# TouScruino-avr-ui2-v0.net
KiCad netlist of a schematic drawn in EAGLE
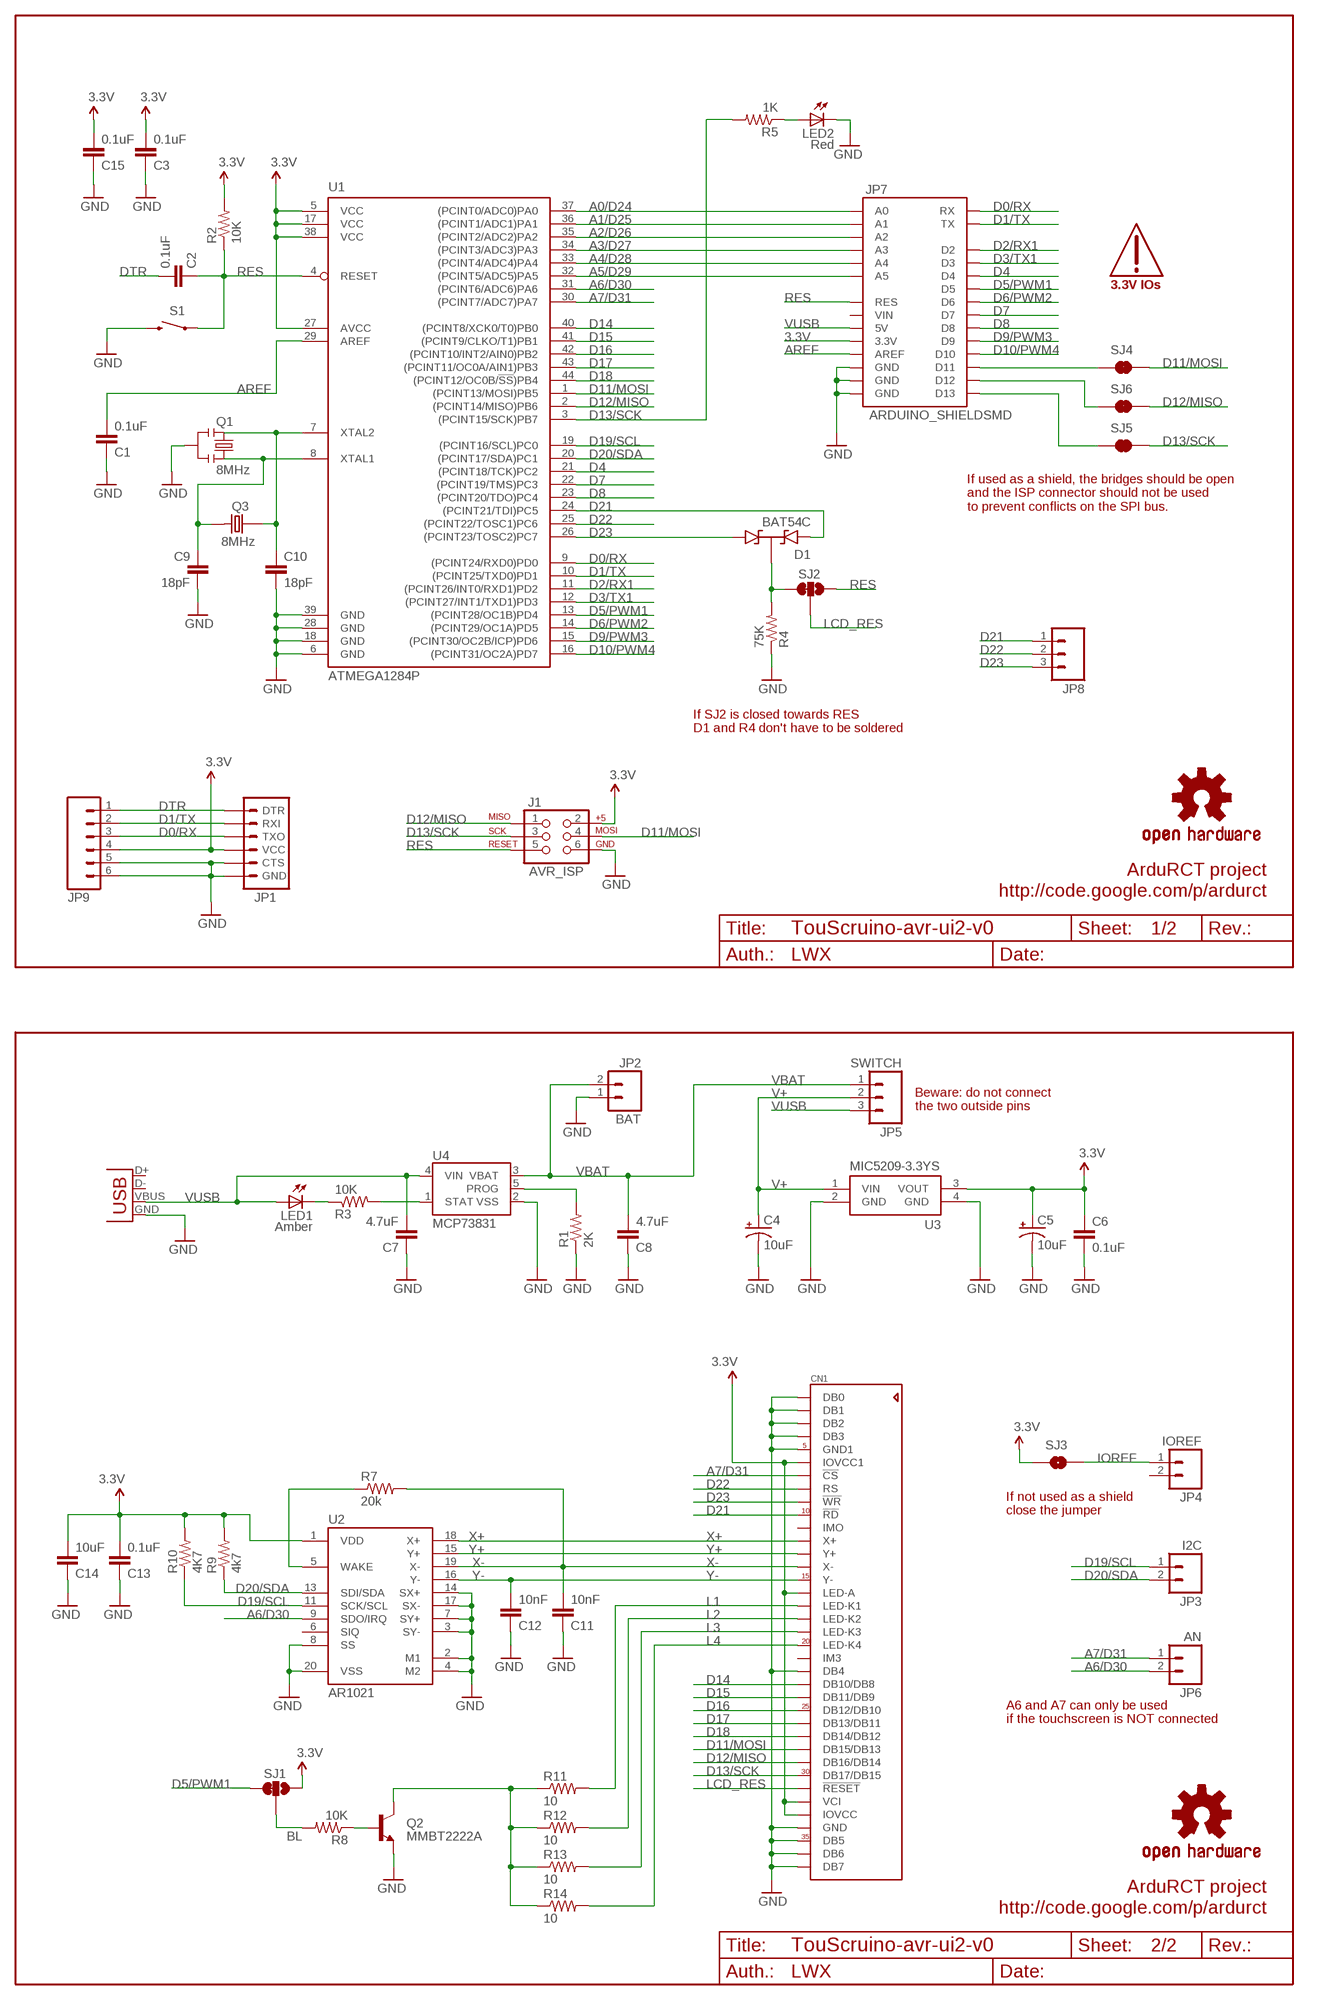
[diagram p0: schematic, sheet 1]

(export (version "E")
  (design (tool "Eeschema 10.0.6"))
  (components
    (comp (ref "C1")
      (value "0.1uF")
      (footprint "eagle-import:0805")
      (libsource (lib "eagle-import") (part "CAP0805"))
    )
    (comp (ref "C2")
      (value "0.1uF")
      (footprint "eagle-import:0805")
      (libsource (lib "eagle-import") (part "CAP0805"))
    )
    (comp (ref "C3")
      (value "0.1uF")
      (footprint "eagle-import:0805")
      (libsource (lib "eagle-import") (part "CAP0805"))
    )
    (comp (ref "C4")
      (value "10uF")
      (footprint "eagle-import:EIA3216")
      (libsource (lib "eagle-import") (part "CAP_POL1206"))
    )
    (comp (ref "C5")
      (value "10uF")
      (footprint "eagle-import:EIA3216")
      (libsource (lib "eagle-import") (part "CAP_POL1206"))
    )
    (comp (ref "C6")
      (value "0.1uF")
      (footprint "eagle-import:0805")
      (libsource (lib "eagle-import") (part "CAP0805"))
    )
    (comp (ref "C7")
      (value "4.7uF")
      (footprint "eagle-import:0805")
      (libsource (lib "eagle-import") (part "CAP0805"))
    )
    (comp (ref "C8")
      (value "4.7uF")
      (footprint "eagle-import:0805")
      (libsource (lib "eagle-import") (part "CAP0805"))
    )
    (comp (ref "C9")
      (value "18pF")
      (footprint "eagle-import:0603-CAP")
      (libsource (lib "eagle-import") (part "CAP0603-CAP"))
    )
    (comp (ref "C10")
      (value "18pF")
      (footprint "eagle-import:0603-CAP")
      (libsource (lib "eagle-import") (part "CAP0603-CAP"))
    )
    (comp (ref "C11")
      (value "10nF")
      (footprint "eagle-import:0805")
      (libsource (lib "eagle-import") (part "CAP0805"))
    )
    (comp (ref "C12")
      (value "10nF")
      (footprint "eagle-import:0805")
      (libsource (lib "eagle-import") (part "CAP0805"))
    )
    (comp (ref "C13")
      (value "0.1uF")
      (footprint "eagle-import:0805")
      (libsource (lib "eagle-import") (part "CAP0805"))
    )
    (comp (ref "C14")
      (value "10uF")
      (footprint "eagle-import:0805")
      (libsource (lib "eagle-import") (part "CAP0805"))
    )
    (comp (ref "C15")
      (value "0.1uF")
      (footprint "eagle-import:0805")
      (libsource (lib "eagle-import") (part "CAP0805"))
    )
    (comp (ref "CN1")
      (value "ILI9325_LCD1.0MM")
      (footprint "eagle-import:ILI9325_28INCH_TS")
      (libsource (lib "eagle-import") (part "ILI9325_LCD1.0MM"))
    )
    (comp (ref "D1")
      (value "BAT54C")
      (footprint "eagle-import:SOT23-3")
      (libsource (lib "eagle-import") (part "BAT54C"))
    )
    (comp (ref "J1")
      (value "AVR_ISP")
      (footprint "eagle-import:2X3")
      (libsource (lib "eagle-import") (part "AVR_SPI_PRG_6PTH"))
    )
    (comp (ref "JP1")
      (value "ARDUINO_SERIAL_PROGRAMPTH")
      (footprint "eagle-import:1X06")
      (libsource (lib "eagle-import") (part "ARDUINO_SERIAL_PROGRAMPTH"))
    )
    (comp (ref "JP2")
      (value "BAT")
      (footprint "eagle-import:JST-2-SMD")
      (libsource (lib "eagle-import") (part "M02-JST-2MM-SMT"))
    )
    (comp (ref "JP3")
      (value "I2C")
      (footprint "eagle-import:1X02_SMD")
      (libsource (lib "eagle-import") (part "M02SMD2"))
    )
    (comp (ref "JP4")
      (value "IOREF")
      (footprint "eagle-import:1X02_SMD")
      (libsource (lib "eagle-import") (part "M02SMD2"))
    )
    (comp (ref "JP5")
      (value "SWITCH")
      (footprint "eagle-import:1X03_SMD_TH")
      (libsource (lib "eagle-import") (part "M03SMD_TH"))
    )
    (comp (ref "JP6")
      (value "AN")
      (footprint "eagle-import:1X02")
      (libsource (lib "eagle-import") (part "M02"))
    )
    (comp (ref "JP7")
      (value "ARDUINO_SHIELDSMD")
      (footprint "eagle-import:ARDUINO_SHIELD_SMD")
      (libsource (lib "eagle-import") (part "ARDUINO_SHIELDSMD"))
    )
    (comp (ref "JP8")
      (value "M03PTH")
      (footprint "eagle-import:1X03")
      (libsource (lib "eagle-import") (part "M03PTH"))
    )
    (comp (ref "JP9")
      (value "M06SMD")
      (footprint "eagle-import:1X06-SMD")
      (libsource (lib "eagle-import") (part "M06SMD"))
    )
    (comp (ref "LED1")
      (value "Amber")
      (footprint "eagle-import:LED")
      (libsource (lib "eagle-import") (part "LED"))
    )
    (comp (ref "LED2")
      (value "Red")
      (footprint "eagle-import:LED")
      (libsource (lib "eagle-import") (part "LED"))
    )
    (comp (ref "Q1")
      (value "8MHz")
      (footprint "eagle-import:RESONATOR-SMD")
      (libsource (lib "eagle-import") (part "RESONATORSMD"))
    )
    (comp (ref "Q2")
      (value "MMBT2222A")
      (footprint "eagle-import:SOT23-3")
      (libsource (lib "eagle-import") (part "TRANSISTOR_NPNSOT23-3"))
    )
    (comp (ref "Q3")
      (value "8MHz")
      (footprint "eagle-import:CRYSTAL_5X3.2")
      (libsource (lib "eagle-import") (part "CRYSTAL_5X3.2"))
    )
    (comp (ref "R1")
      (value "2K")
      (footprint "eagle-import:0805")
      (libsource (lib "eagle-import") (part "RESISTOR0805-RES"))
    )
    (comp (ref "R2")
      (value "10K")
      (footprint "eagle-import:0805")
      (libsource (lib "eagle-import") (part "RESISTOR0805-RES"))
    )
    (comp (ref "R3")
      (value "10K")
      (footprint "eagle-import:0805")
      (libsource (lib "eagle-import") (part "RESISTOR0805-RES"))
    )
    (comp (ref "R4")
      (value "75K")
      (footprint "eagle-import:0805")
      (libsource (lib "eagle-import") (part "RESISTOR0805-RES"))
    )
    (comp (ref "R5")
      (value "1K")
      (footprint "eagle-import:0805")
      (libsource (lib "eagle-import") (part "RESISTOR0805-RES"))
    )
    (comp (ref "R7")
      (value "20k")
      (footprint "eagle-import:0805")
      (libsource (lib "eagle-import") (part "RESISTOR0805-RES"))
    )
    (comp (ref "R8")
      (value "10K")
      (footprint "eagle-import:0805")
      (libsource (lib "eagle-import") (part "RESISTOR0805-RES"))
    )
    (comp (ref "R9")
      (value "4k7")
      (footprint "eagle-import:0805")
      (libsource (lib "eagle-import") (part "RESISTOR0805-RES"))
    )
    (comp (ref "R10")
      (value "4K7")
      (footprint "eagle-import:0805")
      (libsource (lib "eagle-import") (part "RESISTOR0805-RES"))
    )
    (comp (ref "R11")
      (value "10")
      (footprint "eagle-import:0805")
      (libsource (lib "eagle-import") (part "RESISTOR0805-RES"))
    )
    (comp (ref "R12")
      (value "10")
      (footprint "eagle-import:0805")
      (libsource (lib "eagle-import") (part "RESISTOR0805-RES"))
    )
    (comp (ref "R13")
      (value "10")
      (footprint "eagle-import:0805")
      (libsource (lib "eagle-import") (part "RESISTOR0805-RES"))
    )
    (comp (ref "R14")
      (value "10")
      (footprint "eagle-import:0805")
      (libsource (lib "eagle-import") (part "RESISTOR0805-RES"))
    )
    (comp (ref "S1")
      (value "SWITCH-MOMENTARY-2SMD")
      (footprint "eagle-import:TACTILE_SWITCH_SMD")
      (libsource (lib "eagle-import") (part "SWITCH-MOMENTARY-2SMD"))
    )
    (comp (ref "SJ1")
      (value "SJ_2WAYS_1-2")
      (footprint "eagle-import:SJ_2WAYS_1-2_S")
      (libsource (lib "eagle-import") (part "SJ_2WAYS_1-2"))
    )
    (comp (ref "SJ2")
      (value "SJ_2WAYS_1-2")
      (footprint "eagle-import:SJ_2WAYS_1-2_S")
      (libsource (lib "eagle-import") (part "SJ_2WAYS_1-2"))
    )
    (comp (ref "SJ3")
      (value "SOLDERJUMPERNO")
      (footprint "eagle-import:SJ_2S-NO")
      (libsource (lib "eagle-import") (part "SOLDERJUMPERNO"))
    )
    (comp (ref "SJ4")
      (value "SOLDERJUMPERTRACE")
      (footprint "eagle-import:SJ_2S-TRACE")
      (libsource (lib "eagle-import") (part "SOLDERJUMPERTRACE"))
    )
    (comp (ref "SJ5")
      (value "SOLDERJUMPERTRACE")
      (footprint "eagle-import:SJ_2S-TRACE")
      (libsource (lib "eagle-import") (part "SOLDERJUMPERTRACE"))
    )
    (comp (ref "SJ6")
      (value "SOLDERJUMPERTRACE")
      (footprint "eagle-import:SJ_2S-TRACE")
      (libsource (lib "eagle-import") (part "SOLDERJUMPERTRACE"))
    )
    (comp (ref "U$3")
      (value "OSHW-LOGOM")
      (footprint "eagle-import:OSHW-LOGO-M")
      (libsource (lib "eagle-import") (part "OSHW-LOGOM"))
    )
    (comp (ref "U$4")
      (value "3.3V_IO")
      (footprint "eagle-import:3.3V_IO")
      (libsource (lib "eagle-import") (part "3.3V_IO"))
    )
    (comp (ref "U$5")
      (value "OSHW-LOGOM")
      (footprint "eagle-import:OSHW-LOGO-M")
      (libsource (lib "eagle-import") (part "OSHW-LOGOM"))
    )
    (comp (ref "U1")
      (value "ATMEGA1284P")
      (footprint "eagle-import:TQFP44")
      (libsource (lib "eagle-import") (part "ATMEGA324A"))
    )
    (comp (ref "U2")
      (value "AR1021")
      (footprint "eagle-import:SSOP20")
      (libsource (lib "eagle-import") (part "AR1020"))
    )
    (comp (ref "U3")
      (value "MIC5209-3.3YS")
      (footprint "eagle-import:SOT223")
      (libsource (lib "eagle-import") (part "MIC5209"))
    )
    (comp (ref "U4")
      (value "MCP73831")
      (footprint "eagle-import:SOT23-5")
      (libsource (lib "eagle-import") (part "MCP73831"))
    )
    (comp (ref "X2")
      (value "USB")
      (footprint "eagle-import:USB-MICROB")
      (libsource (lib "eagle-import") (part "USB"))
    )
  )
  (nets
    (net (code "1") (name "/A0{slash}D24") (class "Default")
      (node (ref "JP7") (pin "A0") (pinfunction "A0_A0") (pintype "bidirectional"))
      (node (ref "U1") (pin "37") (pinfunction "(PCINT0/ADC0)PA0_37") (pintype "bidirectional"))
    )
    (net (code "2") (name "/A1{slash}D25") (class "Default")
      (node (ref "JP7") (pin "A1") (pinfunction "A1_A1") (pintype "bidirectional"))
      (node (ref "U1") (pin "36") (pinfunction "(PCINT1/ADC1)PA1_36") (pintype "bidirectional"))
    )
    (net (code "3") (name "/A2{slash}D26") (class "Default")
      (node (ref "JP7") (pin "A2") (pinfunction "A2_A2") (pintype "bidirectional"))
      (node (ref "U1") (pin "35") (pinfunction "(PCINT2/ADC2)PA2_35") (pintype "bidirectional"))
    )
    (net (code "4") (name "/A3{slash}D27") (class "Default")
      (node (ref "JP7") (pin "A3") (pinfunction "A3_A3") (pintype "bidirectional"))
      (node (ref "U1") (pin "34") (pinfunction "(PCINT3/ADC3)PA3_34") (pintype "bidirectional"))
    )
    (net (code "5") (name "/A4{slash}D28") (class "Default")
      (node (ref "JP7") (pin "A4") (pinfunction "A4_A4") (pintype "bidirectional"))
      (node (ref "U1") (pin "33") (pinfunction "(PCINT4/ADC4)PA4_33") (pintype "bidirectional"))
    )
    (net (code "6") (name "/A5{slash}D29") (class "Default")
      (node (ref "JP7") (pin "A5") (pinfunction "A5_A5") (pintype "bidirectional"))
      (node (ref "U1") (pin "32") (pinfunction "(PCINT5/ADC5)PA5_32") (pintype "bidirectional"))
    )
    (net (code "7") (name "/A6{slash}D30") (class "Default")
      (node (ref "JP6") (pin "2") (pinfunction "2_2") (pintype "passive"))
      (node (ref "U1") (pin "31") (pinfunction "(PCINT6/ADC6)PA6_31") (pintype "bidirectional"))
      (node (ref "U2") (pin "9") (pinfunction "SDO/IRQ_9") (pintype "bidirectional"))
    )
    (net (code "8") (name "/A7{slash}D31") (class "Default")
      (node (ref "CN1") (pin "7") (pinfunction "~{CS}_7") (pintype "passive"))
      (node (ref "JP6") (pin "1") (pinfunction "1_1") (pintype "passive"))
      (node (ref "U1") (pin "30") (pinfunction "(PCINT7/ADC7)PA7_30") (pintype "bidirectional"))
    )
    (net (code "9") (name "/AREF") (class "Default")
      (node (ref "C1") (pin "2") (pinfunction "2_2") (pintype "passive"))
      (node (ref "JP7") (pin "AREF") (pinfunction "AREF_AREF") (pintype "bidirectional"))
      (node (ref "U1") (pin "29") (pinfunction "AREF_29") (pintype "passive"))
    )
    (net (code "10") (name "/BL") (class "Default")
      (node (ref "R8") (pin "2") (pinfunction "2_2") (pintype "passive"))
      (node (ref "SJ1") (pin "2") (pinfunction "2_2") (pintype "passive"))
    )
    (net (code "11") (name "/D0{slash}RX") (class "Default")
      (node (ref "JP1") (pin "3") (pinfunction "TXO_3") (pintype "passive"))
      (node (ref "JP7") (pin "RX") (pinfunction "RX_RX") (pintype "bidirectional"))
      (node (ref "JP9") (pin "3") (pinfunction "3_3") (pintype "passive"))
      (node (ref "U1") (pin "9") (pinfunction "(PCINT24/RXD0)PD0_9") (pintype "bidirectional"))
    )
    (net (code "12") (name "/D1{slash}TX") (class "Default")
      (node (ref "JP1") (pin "2") (pinfunction "RXI_2") (pintype "passive"))
      (node (ref "JP7") (pin "TX") (pinfunction "TX_TX") (pintype "bidirectional"))
      (node (ref "JP9") (pin "2") (pinfunction "2_2") (pintype "passive"))
      (node (ref "U1") (pin "10") (pinfunction "(PCINT25/TXD0)PD1_10") (pintype "bidirectional"))
    )
    (net (code "13") (name "/D2{slash}RX1") (class "Default")
      (node (ref "JP7") (pin "D2") (pinfunction "D2_D2") (pintype "bidirectional"))
      (node (ref "U1") (pin "11") (pinfunction "(PCINT26/INT0/RXD1)PD2_11") (pintype "bidirectional"))
    )
    (net (code "14") (name "/D3{slash}TX1") (class "Default")
      (node (ref "JP7") (pin "D3") (pinfunction "D3_D3") (pintype "bidirectional"))
      (node (ref "U1") (pin "12") (pinfunction "(PCINT27/INT1/TXD1)PD3_12") (pintype "bidirectional"))
    )
    (net (code "15") (name "/D4") (class "Default")
      (node (ref "JP7") (pin "D4") (pinfunction "D4_D4") (pintype "bidirectional"))
      (node (ref "U1") (pin "21") (pinfunction "(PCINT18/TCK)PC2_21") (pintype "output"))
    )
    (net (code "16") (name "/D5{slash}PWM1") (class "Default")
      (node (ref "JP7") (pin "D5") (pinfunction "D5_D5") (pintype "bidirectional"))
      (node (ref "SJ1") (pin "1") (pinfunction "1_1") (pintype "passive"))
      (node (ref "U1") (pin "13") (pinfunction "(PCINT28/OC1B)PD4_13") (pintype "bidirectional"))
    )
    (net (code "17") (name "/D6{slash}PWM2") (class "Default")
      (node (ref "JP7") (pin "D6") (pinfunction "D6_D6") (pintype "bidirectional"))
      (node (ref "U1") (pin "14") (pinfunction "(PCINT29/OC1A)PD5_14") (pintype "bidirectional"))
    )
    (net (code "18") (name "/D7") (class "Default")
      (node (ref "JP7") (pin "D7") (pinfunction "D7_D7") (pintype "bidirectional"))
      (node (ref "U1") (pin "22") (pinfunction "(PCINT19/TMS)PC3_22") (pintype "output"))
    )
    (net (code "19") (name "/D8") (class "Default")
      (node (ref "JP7") (pin "D8") (pinfunction "D8_D8") (pintype "bidirectional"))
      (node (ref "U1") (pin "23") (pinfunction "(PCINT20/TDO)PC4_23") (pintype "output"))
    )
    (net (code "20") (name "/D9{slash}PWM3") (class "Default")
      (node (ref "JP7") (pin "D9") (pinfunction "D9_D9") (pintype "bidirectional"))
      (node (ref "U1") (pin "15") (pinfunction "(PCINT30/OC2B/ICP)PD6_15") (pintype "bidirectional"))
    )
    (net (code "21") (name "/D10{slash}PWM4") (class "Default")
      (node (ref "JP7") (pin "D10") (pinfunction "D10_D10") (pintype "bidirectional"))
      (node (ref "U1") (pin "16") (pinfunction "(PCINT31/OC2A)PD7_16") (pintype "bidirectional"))
    )
    (net (code "22") (name "/D11{slash}MOSI") (class "Default")
      (node (ref "CN1") (pin "28") (pinfunction "DB15/DB13_28") (pintype "passive"))
      (node (ref "J1") (pin "4") (pinfunction "4_4") (pintype "passive"))
      (node (ref "SJ4") (pin "2") (pinfunction "2_2") (pintype "passive"))
      (node (ref "U1") (pin "1") (pinfunction "(PCINT13/MOSI)PB5_1") (pintype "bidirectional"))
    )
    (net (code "23") (name "/D12{slash}MISO") (class "Default")
      (node (ref "CN1") (pin "29") (pinfunction "DB16/DB14_29") (pintype "passive"))
      (node (ref "J1") (pin "1") (pinfunction "1_1") (pintype "passive"))
      (node (ref "SJ6") (pin "2") (pinfunction "2_2") (pintype "passive"))
      (node (ref "U1") (pin "2") (pinfunction "(PCINT14/MISO)PB6_2") (pintype "bidirectional"))
    )
    (net (code "24") (name "/D13{slash}SCK") (class "Default")
      (node (ref "CN1") (pin "30") (pinfunction "DB17/DB15_30") (pintype "passive"))
      (node (ref "J1") (pin "3") (pinfunction "3_3") (pintype "passive"))
      (node (ref "R5") (pin "2") (pinfunction "2_2") (pintype "passive"))
      (node (ref "SJ5") (pin "2") (pinfunction "2_2") (pintype "passive"))
      (node (ref "U1") (pin "3") (pinfunction "(PCINT15/SCK)PB7_3") (pintype "bidirectional"))
    )
    (net (code "25") (name "/D14") (class "Default")
      (node (ref "CN1") (pin "23") (pinfunction "DB10/DB8_23") (pintype "passive"))
      (node (ref "U1") (pin "40") (pinfunction "(PCINT8/XCK0/T0)PB0_40") (pintype "bidirectional"))
    )
    (net (code "26") (name "/D15") (class "Default")
      (node (ref "CN1") (pin "24") (pinfunction "DB11/DB9_24") (pintype "passive"))
      (node (ref "U1") (pin "41") (pinfunction "(PCINT9/CLKO/T1)PB1_41") (pintype "bidirectional"))
    )
    (net (code "27") (name "/D16") (class "Default")
      (node (ref "CN1") (pin "25") (pinfunction "DB12/DB10_25") (pintype "passive"))
      (node (ref "U1") (pin "42") (pinfunction "(PCINT10/INT2/AIN0)PB2_42") (pintype "bidirectional"))
    )
    (net (code "28") (name "/D17") (class "Default")
      (node (ref "CN1") (pin "26") (pinfunction "DB13/DB11_26") (pintype "passive"))
      (node (ref "U1") (pin "43") (pinfunction "(PCINT11/OC0A/AIN1)PB3_43") (pintype "bidirectional"))
    )
    (net (code "29") (name "/D18") (class "Default")
      (node (ref "CN1") (pin "27") (pinfunction "DB14/DB12_27") (pintype "passive"))
      (node (ref "U1") (pin "44") (pinfunction "(PCINT12/OC0B/~{SS})PB4_44") (pintype "bidirectional"))
    )
    (net (code "30") (name "/D19{slash}SCL") (class "Default")
      (node (ref "JP3") (pin "1") (pinfunction "1_1") (pintype "passive"))
      (node (ref "R10") (pin "1") (pinfunction "1_1") (pintype "passive"))
      (node (ref "U1") (pin "19") (pinfunction "(PCINT16/SCL)PC0_19") (pintype "output"))
      (node (ref "U2") (pin "11") (pinfunction "SCK/SCL_11") (pintype "bidirectional"))
    )
    (net (code "31") (name "/D20{slash}SDA") (class "Default")
      (node (ref "JP3") (pin "2") (pinfunction "2_2") (pintype "passive"))
      (node (ref "R9") (pin "1") (pinfunction "1_1") (pintype "passive"))
      (node (ref "U1") (pin "20") (pinfunction "(PCINT17/SDA)PC1_20") (pintype "output"))
      (node (ref "U2") (pin "13") (pinfunction "SDI/SDA_13") (pintype "bidirectional"))
    )
    (net (code "32") (name "/D21") (class "Default")
      (node (ref "CN1") (pin "10") (pinfunction "~{RD}_10") (pintype "passive"))
      (node (ref "D1") (pin "2") (pinfunction "A2_2") (pintype "bidirectional"))
      (node (ref "JP8") (pin "1") (pinfunction "1_1") (pintype "passive"))
      (node (ref "U1") (pin "24") (pinfunction "(PCINT21/TDI)PC5_24") (pintype "output"))
    )
    (net (code "33") (name "/D22") (class "Default")
      (node (ref "CN1") (pin "8") (pinfunction "RS_8") (pintype "passive"))
      (node (ref "JP8") (pin "2") (pinfunction "2_2") (pintype "passive"))
      (node (ref "U1") (pin "25") (pinfunction "(PCINT22/TOSC1)PC6_25") (pintype "output"))
    )
    (net (code "34") (name "/D23") (class "Default")
      (node (ref "CN1") (pin "9") (pinfunction "~{WR}_9") (pintype "passive"))
      (node (ref "D1") (pin "1") (pinfunction "A1_1") (pintype "bidirectional"))
      (node (ref "JP8") (pin "3") (pinfunction "3_3") (pintype "passive"))
      (node (ref "U1") (pin "26") (pinfunction "(PCINT23/TOSC2)PC7_26") (pintype "output"))
    )
    (net (code "35") (name "/DTR") (class "Default")
      (node (ref "C2") (pin "2") (pinfunction "2_2") (pintype "passive"))
      (node (ref "JP1") (pin "1") (pinfunction "DTR_1") (pintype "passive"))
      (node (ref "JP9") (pin "1") (pinfunction "1_1") (pintype "passive"))
    )
    (net (code "36") (name "/IOREF") (class "Default")
      (node (ref "JP4") (pin "1") (pinfunction "1_1") (pintype "passive"))
      (node (ref "SJ3") (pin "2") (pinfunction "2_2") (pintype "passive"))
    )
    (net (code "37") (name "/L1") (class "Default")
      (node (ref "CN1") (pin "17") (pinfunction "LED-K1_17") (pintype "passive"))
      (node (ref "R11") (pin "2") (pinfunction "2_2") (pintype "passive"))
    )
    (net (code "38") (name "/L2") (class "Default")
      (node (ref "CN1") (pin "18") (pinfunction "LED-K2_18") (pintype "passive"))
      (node (ref "R12") (pin "2") (pinfunction "2_2") (pintype "passive"))
    )
    (net (code "39") (name "/L3") (class "Default")
      (node (ref "CN1") (pin "19") (pinfunction "LED-K3_19") (pintype "passive"))
      (node (ref "R13") (pin "2") (pinfunction "2_2") (pintype "passive"))
    )
    (net (code "40") (name "/L4") (class "Default")
      (node (ref "CN1") (pin "20") (pinfunction "LED-K4_20") (pintype "passive"))
      (node (ref "R14") (pin "2") (pinfunction "2_2") (pintype "passive"))
    )
    (net (code "41") (name "/LCD_RES") (class "Default")
      (node (ref "CN1") (pin "31") (pinfunction "~{RESET}_31") (pintype "passive"))
      (node (ref "SJ2") (pin "2") (pinfunction "2_2") (pintype "passive"))
    )
    (net (code "42") (name "/RES") (class "Default")
      (node (ref "C2") (pin "1") (pinfunction "1_1") (pintype "passive"))
      (node (ref "J1") (pin "5") (pinfunction "5_5") (pintype "passive"))
      (node (ref "JP7") (pin "RES") (pinfunction "RES_RES") (pintype "bidirectional"))
      (node (ref "R2") (pin "1") (pinfunction "1_1") (pintype "passive"))
      (node (ref "S1") (pin "1") (pinfunction "1_1") (pintype "passive"))
      (node (ref "SJ2") (pin "3") (pinfunction "3_3") (pintype "passive"))
      (node (ref "U1") (pin "4") (pinfunction "RESET_4") (pintype "input"))
    )
    (net (code "43") (name "/V+") (class "Default")
      (node (ref "C4") (pin "A") (pinfunction "+_A") (pintype "passive"))
      (node (ref "JP5") (pin "2") (pinfunction "2_2") (pintype "passive"))
      (node (ref "U3") (pin "1") (pinfunction "VIN_1") (pintype "bidirectional"))
    )
    (net (code "44") (name "/VBAT") (class "Default")
      (node (ref "C8") (pin "2") (pinfunction "2_2") (pintype "passive"))
      (node (ref "JP2") (pin "2") (pinfunction "2_2") (pintype "passive"))
      (node (ref "JP5") (pin "1") (pinfunction "1_1") (pintype "passive"))
      (node (ref "U4") (pin "3") (pinfunction "VBAT_3") (pintype "power_in"))
    )
    (net (code "45") (name "/VUSB") (class "Default")
      (node (ref "C7") (pin "2") (pinfunction "2_2") (pintype "passive"))
      (node (ref "JP5") (pin "3") (pinfunction "3_3") (pintype "passive"))
      (node (ref "JP7") (pin "5V") (pinfunction "5V_5V") (pintype "bidirectional"))
      (node (ref "LED1") (pin "A1") (pinfunction "A_A1") (pintype "passive"))
      (node (ref "U4") (pin "4") (pinfunction "VIN_4") (pintype "power_in"))
      (node (ref "X2") (pin "VBUS") (pinfunction "VBUS_VBUS") (pintype "bidirectional"))
    )
    (net (code "46") (name "/X+") (class "Default")
      (node (ref "CN1") (pin "12") (pinfunction "X+_12") (pintype "passive"))
      (node (ref "U2") (pin "18") (pinfunction "X+_18") (pintype "bidirectional"))
    )
    (net (code "47") (name "/X-") (class "Default")
      (node (ref "C11") (pin "2") (pinfunction "2_2") (pintype "passive"))
      (node (ref "CN1") (pin "14") (pinfunction "X-_14") (pintype "passive"))
      (node (ref "R7") (pin "2") (pinfunction "2_2") (pintype "passive"))
      (node (ref "U2") (pin "19") (pinfunction "X-_19") (pintype "bidirectional"))
    )
    (net (code "48") (name "/Y+") (class "Default")
      (node (ref "CN1") (pin "13") (pinfunction "Y+_13") (pintype "passive"))
      (node (ref "U2") (pin "15") (pinfunction "Y+_15") (pintype "bidirectional"))
    )
    (net (code "49") (name "/Y-") (class "Default")
      (node (ref "C12") (pin "2") (pinfunction "2_2") (pintype "passive"))
      (node (ref "CN1") (pin "15") (pinfunction "Y-_15") (pintype "passive"))
      (node (ref "U2") (pin "16") (pinfunction "Y-_16") (pintype "bidirectional"))
    )
    (net (code "50") (name "3.3V") (class "Default")
      (node (ref "C13") (pin "2") (pinfunction "2_2") (pintype "passive"))
      (node (ref "C14") (pin "2") (pinfunction "2_2") (pintype "passive"))
      (node (ref "C15") (pin "2") (pinfunction "2_2") (pintype "passive"))
      (node (ref "C3") (pin "2") (pinfunction "2_2") (pintype "passive"))
      (node (ref "C5") (pin "A") (pinfunction "+_A") (pintype "passive"))
      (node (ref "C6") (pin "1") (pinfunction "1_1") (pintype "passive"))
      (node (ref "CN1") (pin "16") (pinfunction "LED-A_16") (pintype "passive"))
      (node (ref "CN1") (pin "32") (pinfunction "VCI_32") (pintype "power_in"))
      (node (ref "CN1") (pin "33") (pinfunction "IOVCC_33") (pintype "power_in"))
      (node (ref "CN1") (pin "6") (pinfunction "IOVCC1_6") (pintype "power_in"))
      (node (ref "J1") (pin "2") (pinfunction "2_2") (pintype "passive"))
      (node (ref "JP1") (pin "4") (pinfunction "VCC_4") (pintype "passive"))
      (node (ref "JP7") (pin "3.3V") (pinfunction "3.3V_3.3V") (pintype "bidirectional"))
      (node (ref "JP9") (pin "4") (pinfunction "4_4") (pintype "passive"))
      (node (ref "R10") (pin "2") (pinfunction "2_2") (pintype "passive"))
      (node (ref "R2") (pin "2") (pinfunction "2_2") (pintype "passive"))
      (node (ref "R9") (pin "2") (pinfunction "2_2") (pintype "passive"))
      (node (ref "SJ1") (pin "3") (pinfunction "3_3") (pintype "passive"))
      (node (ref "SJ3") (pin "1") (pinfunction "1_1") (pintype "passive"))
      (node (ref "U1") (pin "17") (pinfunction "VCC_17") (pintype "power_in"))
      (node (ref "U1") (pin "27") (pinfunction "AVCC_27") (pintype "power_in"))
      (node (ref "U1") (pin "38") (pinfunction "VCC_38") (pintype "power_in"))
      (node (ref "U1") (pin "5") (pinfunction "VCC_5") (pintype "power_in"))
      (node (ref "U2") (pin "1") (pinfunction "VDD_1") (pintype "bidirectional"))
      (node (ref "U3") (pin "3") (pinfunction "VOUT_3") (pintype "bidirectional"))
    )
    (net (code "51") (name "GND") (class "Default")
      (node (ref "C1") (pin "1") (pinfunction "1_1") (pintype "passive"))
      (node (ref "C10") (pin "2") (pinfunction "2_2") (pintype "passive"))
      (node (ref "C11") (pin "1") (pinfunction "1_1") (pintype "passive"))
      (node (ref "C12") (pin "1") (pinfunction "1_1") (pintype "passive"))
      (node (ref "C13") (pin "1") (pinfunction "1_1") (pintype "passive"))
      (node (ref "C14") (pin "1") (pinfunction "1_1") (pintype "passive"))
      (node (ref "C15") (pin "1") (pinfunction "1_1") (pintype "passive"))
      (node (ref "C3") (pin "1") (pinfunction "1_1") (pintype "passive"))
      (node (ref "C4") (pin "C") (pinfunction "-_C") (pintype "passive"))
      (node (ref "C5") (pin "C") (pinfunction "-_C") (pintype "passive"))
      (node (ref "C6") (pin "2") (pinfunction "2_2") (pintype "passive"))
      (node (ref "C7") (pin "1") (pinfunction "1_1") (pintype "passive"))
      (node (ref "C8") (pin "1") (pinfunction "1_1") (pintype "passive"))
      (node (ref "C9") (pin "2") (pinfunction "2_2") (pintype "passive"))
      (node (ref "CN1") (pin "1") (pinfunction "DB0_1") (pintype "passive"))
      (node (ref "CN1") (pin "2") (pinfunction "DB1_2") (pintype "passive"))
      (node (ref "CN1") (pin "22") (pinfunction "DB4_22") (pintype "passive"))
      (node (ref "CN1") (pin "3") (pinfunction "DB2_3") (pintype "passive"))
      (node (ref "CN1") (pin "34") (pinfunction "GND_34") (pintype "power_in"))
      (node (ref "CN1") (pin "35") (pinfunction "DB5_35") (pintype "passive"))
      (node (ref "CN1") (pin "36") (pinfunction "DB6_36") (pintype "passive"))
      (node (ref "CN1") (pin "37") (pinfunction "DB7_37") (pintype "passive"))
      (node (ref "CN1") (pin "4") (pinfunction "DB3_4") (pintype "passive"))
      (node (ref "CN1") (pin "5") (pinfunction "GND1_5") (pintype "power_in"))
      (node (ref "J1") (pin "6") (pinfunction "6_6") (pintype "passive"))
      (node (ref "JP1") (pin "5") (pinfunction "CTS_5") (pintype "passive"))
      (node (ref "JP1") (pin "6") (pinfunction "GND_6") (pintype "passive"))
      (node (ref "JP2") (pin "1") (pinfunction "1_1") (pintype "passive"))
      (node (ref "JP7") (pin "GND@0") (pinfunction "GND_GND@0") (pintype "bidirectional"))
      (node (ref "JP7") (pin "GND@1") (pinfunction "GND_GND@1") (pintype "bidirectional"))
      (node (ref "JP7") (pin "GND@2") (pinfunction "GND_GND@2") (pintype "bidirectional"))
      (node (ref "JP9") (pin "5") (pinfunction "5_5") (pintype "passive"))
      (node (ref "JP9") (pin "6") (pinfunction "6_6") (pintype "passive"))
      (node (ref "LED2") (pin "C1") (pinfunction "C_C1") (pintype "passive"))
      (node (ref "Q1") (pin "2") (pinfunction "2_2") (pintype "passive"))
      (node (ref "Q2") (pin "2") (pinfunction "E_2") (pintype "passive"))
      (node (ref "R1") (pin "1") (pinfunction "1_1") (pintype "passive"))
      (node (ref "R4") (pin "1") (pinfunction "1_1") (pintype "passive"))
      (node (ref "S1") (pin "3") (pinfunction "2_3") (pintype "passive"))
      (node (ref "U1") (pin "18") (pinfunction "GND_18") (pintype "power_in"))
      (node (ref "U1") (pin "28") (pinfunction "GND_28") (pintype "power_in"))
      (node (ref "U1") (pin "39") (pinfunction "GND_39") (pintype "power_in"))
      (node (ref "U1") (pin "6") (pinfunction "GND_6") (pintype "power_in"))
      (node (ref "U2") (pin "14") (pinfunction "SX+_14") (pintype "bidirectional"))
      (node (ref "U2") (pin "17") (pinfunction "SX-_17") (pintype "bidirectional"))
      (node (ref "U2") (pin "2") (pinfunction "M1_2") (pintype "bidirectional"))
      (node (ref "U2") (pin "20") (pinfunction "VSS_20") (pintype "bidirectional"))
      (node (ref "U2") (pin "3") (pinfunction "SY-_3") (pintype "bidirectional"))
      (node (ref "U2") (pin "4") (pinfunction "M2_4") (pintype "bidirectional"))
      (node (ref "U2") (pin "7") (pinfunction "SY+_7") (pintype "bidirectional"))
      (node (ref "U2") (pin "8") (pinfunction "SS_8") (pintype "bidirectional"))
      (node (ref "U3") (pin "2") (pinfunction "GND_2") (pintype "bidirectional"))
      (node (ref "U3") (pin "4") (pinfunction "GND_4") (pintype "bidirectional"))
      (node (ref "U4") (pin "2") (pinfunction "VSS_2") (pintype "power_in"))
      (node (ref "X2") (pin "GND") (pinfunction "GND_GND") (pintype "bidirectional"))
    )
    (net (code "52") (name "Net-(D1-K)") (class "Default")
      (node (ref "D1") (pin "3") (pinfunction "K_3") (pintype "bidirectional"))
      (node (ref "R4") (pin "2") (pinfunction "2_2") (pintype "passive"))
      (node (ref "SJ2") (pin "1") (pinfunction "1_1") (pintype "passive"))
    )
    (net (code "53") (name "Net-(JP7-PadD11)") (class "Default")
      (node (ref "JP7") (pin "D11") (pinfunction "D11_D11") (pintype "bidirectional"))
      (node (ref "SJ4") (pin "1") (pinfunction "1_1") (pintype "passive"))
    )
    (net (code "54") (name "Net-(JP7-PadD12)") (class "Default")
      (node (ref "JP7") (pin "D12") (pinfunction "D12_D12") (pintype "bidirectional"))
      (node (ref "SJ6") (pin "1") (pinfunction "1_1") (pintype "passive"))
    )
    (net (code "55") (name "Net-(JP7-PadD13)") (class "Default")
      (node (ref "JP7") (pin "D13") (pinfunction "D13_D13") (pintype "bidirectional"))
      (node (ref "SJ5") (pin "1") (pinfunction "1_1") (pintype "passive"))
    )
    (net (code "56") (name "Net-(LED1-C)") (class "Default")
      (node (ref "LED1") (pin "C1") (pinfunction "C_C1") (pintype "passive"))
      (node (ref "R3") (pin "1") (pinfunction "1_1") (pintype "passive"))
    )
    (net (code "57") (name "Net-(LED2-A)") (class "Default")
      (node (ref "LED2") (pin "A1") (pinfunction "A_A1") (pintype "passive"))
      (node (ref "R5") (pin "1") (pinfunction "1_1") (pintype "passive"))
    )
    (net (code "58") (name "Net-(Q2-B)") (class "Default")
      (node (ref "Q2") (pin "1") (pinfunction "B_1") (pintype "passive"))
      (node (ref "R8") (pin "1") (pinfunction "1_1") (pintype "passive"))
    )
    (net (code "59") (name "Net-(Q2-C)") (class "Default")
      (node (ref "Q2") (pin "3") (pinfunction "C_3") (pintype "passive"))
      (node (ref "R11") (pin "1") (pinfunction "1_1") (pintype "passive"))
      (node (ref "R12") (pin "1") (pinfunction "1_1") (pintype "passive"))
      (node (ref "R13") (pin "1") (pinfunction "1_1") (pintype "passive"))
      (node (ref "R14") (pin "1") (pinfunction "1_1") (pintype "passive"))
    )
    (net (code "60") (name "Net-(U1-XTAL1)") (class "Default")
      (node (ref "C9") (pin "1") (pinfunction "1_1") (pintype "passive"))
      (node (ref "Q1") (pin "1") (pinfunction "1_1") (pintype "passive"))
      (node (ref "Q3") (pin "2") (pinfunction "2_2") (pintype "passive"))
      (node (ref "U1") (pin "8") (pinfunction "XTAL1_8") (pintype "bidirectional"))
    )
    (net (code "61") (name "Net-(U1-XTAL2)") (class "Default")
      (node (ref "C10") (pin "1") (pinfunction "1_1") (pintype "passive"))
      (node (ref "Q1") (pin "3") (pinfunction "3_3") (pintype "passive"))
      (node (ref "Q3") (pin "1") (pinfunction "1_1") (pintype "passive"))
      (node (ref "U1") (pin "7") (pinfunction "XTAL2_7") (pintype "bidirectional"))
    )
    (net (code "62") (name "Net-(U2-WAKE)") (class "Default")
      (node (ref "R7") (pin "1") (pinfunction "1_1") (pintype "passive"))
      (node (ref "U2") (pin "5") (pinfunction "WAKE_5") (pintype "bidirectional"))
    )
    (net (code "63") (name "Net-(U4-PROG)") (class "Default")
      (node (ref "R1") (pin "2") (pinfunction "2_2") (pintype "passive"))
      (node (ref "U4") (pin "5") (pinfunction "PROG_5") (pintype "input"))
    )
    (net (code "64") (name "Net-(U4-STAT)") (class "Default")
      (node (ref "R3") (pin "2") (pinfunction "2_2") (pintype "passive"))
      (node (ref "U4") (pin "1") (pinfunction "STAT_1") (pintype "output"))
    )
    (net (code "65") (name "unconnected-(CN1-IM3-Pad21)") (class "Default")
      (node (ref "CN1") (pin "21") (pinfunction "IM3_21") (pintype "passive"))
    )
    (net (code "66") (name "unconnected-(CN1-IMO-Pad11)") (class "Default")
      (node (ref "CN1") (pin "11") (pinfunction "IMO_11") (pintype "passive"))
    )
    (net (code "67") (name "unconnected-(JP4-Pad2)") (class "Default")
      (node (ref "JP4") (pin "2") (pinfunction "2_2") (pintype "passive"))
    )
    (net (code "68") (name "unconnected-(JP7-PadVIN)") (class "Default")
      (node (ref "JP7") (pin "VIN") (pinfunction "VIN_VIN") (pintype "bidirectional"))
    )
    (net (code "69") (name "unconnected-(U2-SIQ-Pad6)") (class "Default")
      (node (ref "U2") (pin "6") (pinfunction "SIQ_6") (pintype "bidirectional"))
    )
    (net (code "70") (name "unconnected-(X2-PadD+)") (class "Default")
      (node (ref "X2") (pin "D+") (pinfunction "D+_D+") (pintype "bidirectional"))
    )
    (net (code "71") (name "unconnected-(X2-PadD-)") (class "Default")
      (node (ref "X2") (pin "D-") (pinfunction "D-_D-") (pintype "bidirectional"))
    )
  )
)
